# sif_mod.net
KiCad netlist of a schematic drawn in EAGLE
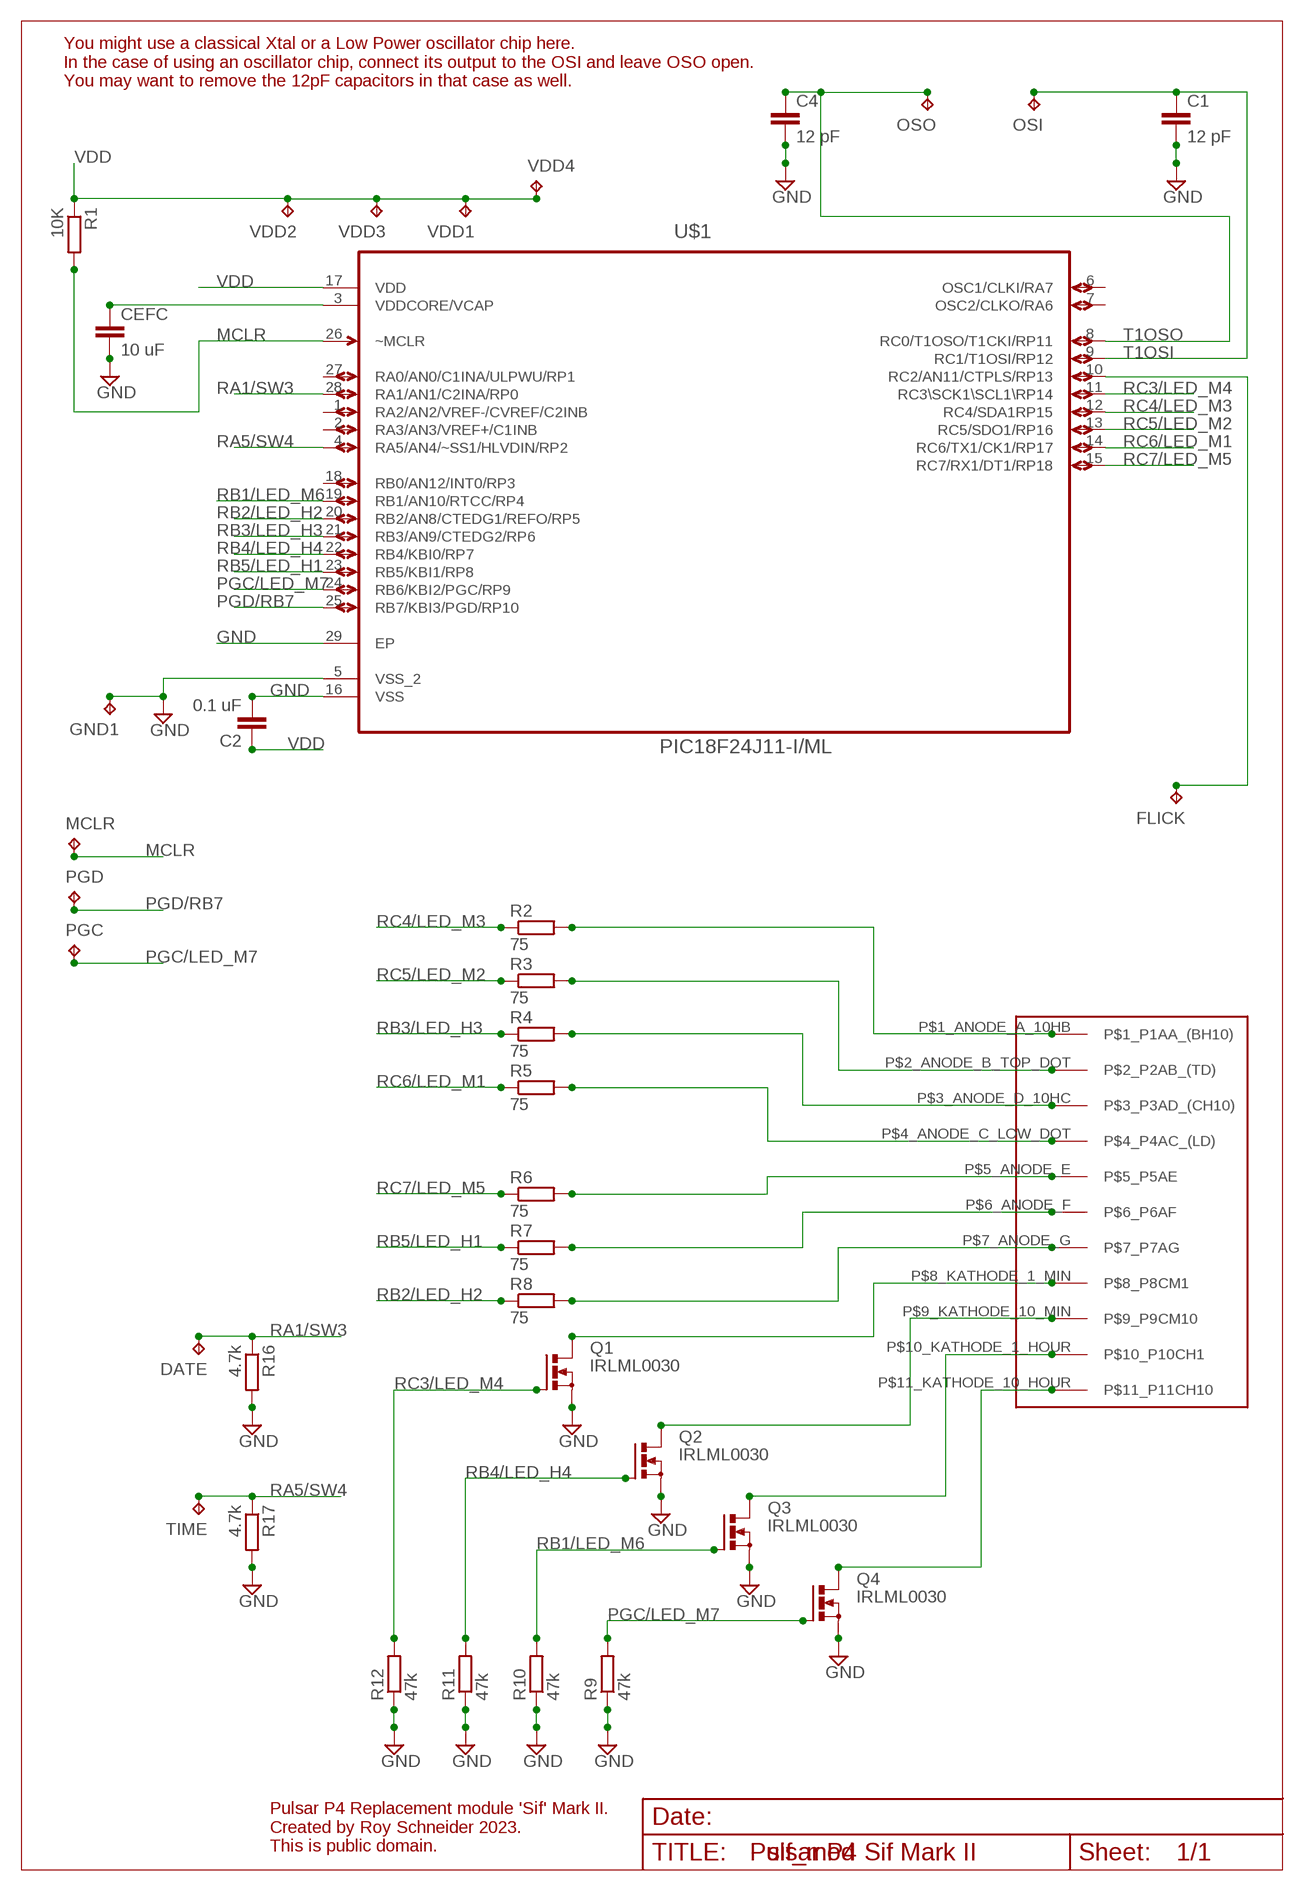
[diagram p0: schematic, sheet 1]

(export (version "E")
  (design (tool "Eeschema 10.0.6"))
  (components
    (comp (ref "C1")
      (value "12 pF")
      (footprint "eagle-import:C0402K")
      (libsource (lib "eagle-import") (part "resistor_mod_C-EUC0402K"))
    )
    (comp (ref "C2")
      (value "0.1 uF")
      (footprint "eagle-import:C0402K")
      (libsource (lib "eagle-import") (part "resistor_mod_C-EUC0402K"))
    )
    (comp (ref "C4")
      (value "12 pF")
      (footprint "eagle-import:C0402K")
      (libsource (lib "eagle-import") (part "resistor_mod_C-EUC0402K"))
    )
    (comp (ref "CEFC")
      (value "10 uF")
      (footprint "eagle-import:C0603")
      (libsource (lib "eagle-import") (part "C-EUC0603"))
    )
    (comp (ref "DATE")
      (value "TPTP08SQ")
      (footprint "eagle-import:TP08SQ")
      (libsource (lib "eagle-import") (part "TPTP08SQ"))
    )
    (comp (ref "FLICK")
      (value "TPTP08SQ")
      (footprint "eagle-import:TP08SQ")
      (libsource (lib "eagle-import") (part "TPTP08SQ"))
    )
    (comp (ref "GND1")
      (value "TPTP08SQ")
      (footprint "eagle-import:TP08SQ")
      (libsource (lib "eagle-import") (part "TPTP08SQ"))
    )
    (comp (ref "MCLR")
      (value "TPTP06SQ")
      (footprint "eagle-import:TP06SQ")
      (libsource (lib "eagle-import") (part "TPTP06SQ"))
    )
    (comp (ref "OSI")
      (value "TPTP08SQ")
      (footprint "eagle-import:TP08SQ")
      (libsource (lib "eagle-import") (part "TPTP08SQ"))
    )
    (comp (ref "OSO")
      (value "TPTP08SQ")
      (footprint "eagle-import:TP08SQ")
      (libsource (lib "eagle-import") (part "TPTP08SQ"))
    )
    (comp (ref "PGC")
      (value "TPTP06SQ")
      (footprint "eagle-import:TP06SQ")
      (libsource (lib "eagle-import") (part "TPTP06SQ"))
    )
    (comp (ref "PGD")
      (value "TPTP06SQ")
      (footprint "eagle-import:TP06SQ")
      (libsource (lib "eagle-import") (part "TPTP06SQ"))
    )
    (comp (ref "Q1")
      (value "IRLML0030")
      (footprint "eagle-import:SOT-23")
      (libsource (lib "eagle-import") (part "IRLML0030"))
    )
    (comp (ref "Q2")
      (value "IRLML0030")
      (footprint "eagle-import:SOT-23")
      (libsource (lib "eagle-import") (part "IRLML0030"))
    )
    (comp (ref "Q3")
      (value "IRLML0030")
      (footprint "eagle-import:SOT-23")
      (libsource (lib "eagle-import") (part "IRLML0030"))
    )
    (comp (ref "Q4")
      (value "IRLML0030")
      (footprint "eagle-import:SOT-23")
      (libsource (lib "eagle-import") (part "IRLML0030"))
    )
    (comp (ref "R1")
      (value "10K")
      (footprint "eagle-import:R0402")
      (libsource (lib "eagle-import") (part "R-EU_R0402"))
    )
    (comp (ref "R2")
      (value "75")
      (footprint "eagle-import:R0402")
      (libsource (lib "eagle-import") (part "R-EU_R0402"))
    )
    (comp (ref "R3")
      (value "75")
      (footprint "eagle-import:R0402")
      (libsource (lib "eagle-import") (part "R-EU_R0402"))
    )
    (comp (ref "R4")
      (value "75")
      (footprint "eagle-import:R0402")
      (libsource (lib "eagle-import") (part "R-EU_R0402"))
    )
    (comp (ref "R5")
      (value "75")
      (footprint "eagle-import:R0402")
      (libsource (lib "eagle-import") (part "R-EU_R0402"))
    )
    (comp (ref "R6")
      (value "75")
      (footprint "eagle-import:R0402")
      (libsource (lib "eagle-import") (part "R-EU_R0402"))
    )
    (comp (ref "R7")
      (value "75")
      (footprint "eagle-import:R0402")
      (libsource (lib "eagle-import") (part "R-EU_R0402"))
    )
    (comp (ref "R8")
      (value "75")
      (footprint "eagle-import:R0402")
      (libsource (lib "eagle-import") (part "R-EU_R0402"))
    )
    (comp (ref "R9")
      (value "47k")
      (footprint "eagle-import:R0402")
      (libsource (lib "eagle-import") (part "R-EU_R0402"))
    )
    (comp (ref "R10")
      (value "47k")
      (footprint "eagle-import:R0402")
      (libsource (lib "eagle-import") (part "R-EU_R0402"))
    )
    (comp (ref "R11")
      (value "47k")
      (footprint "eagle-import:R0402")
      (libsource (lib "eagle-import") (part "R-EU_R0402"))
    )
    (comp (ref "R12")
      (value "47k")
      (footprint "eagle-import:R0402")
      (libsource (lib "eagle-import") (part "R-EU_R0402"))
    )
    (comp (ref "R16")
      (value "4.7k")
      (footprint "eagle-import:R0402")
      (libsource (lib "eagle-import") (part "R-EU_R0402"))
    )
    (comp (ref "R17")
      (value "4.7k")
      (footprint "eagle-import:R0402")
      (libsource (lib "eagle-import") (part "R-EU_R0402"))
    )
    (comp (ref "TIME")
      (value "TPTP08SQ")
      (footprint "eagle-import:TP08SQ")
      (libsource (lib "eagle-import") (part "TPTP08SQ"))
    )
    (comp (ref "U$1")
      (value "PIC18F24J11-I/ML")
      (footprint "eagle-import:QFN65P600X600X100-29N")
      (fields (field (name "MPN") "PIC18F24J11-I/Ml"))
      (libsource (lib "eagle-import") (part "PIC18F24J11-I/ML"))
    )
    (comp (ref "U$2")
      (value "PULSAR_P4_DISPLAYPULSAR_P4_LED_DISPLAY")
      (footprint "eagle-import:PULSAR_P3_LED_DISPLAY")
      (libsource (lib "eagle-import") (part "PULSAR_P4_DISPLAYPULSAR_P4_LED_DISPLAY"))
    )
    (comp (ref "VDD1")
      (value "TPTP08SQ")
      (footprint "eagle-import:TP08SQ")
      (libsource (lib "eagle-import") (part "TPTP08SQ"))
    )
    (comp (ref "VDD2")
      (value "TPTP08SQ")
      (footprint "eagle-import:TP08SQ")
      (libsource (lib "eagle-import") (part "TPTP08SQ"))
    )
    (comp (ref "VDD3")
      (value "TPTP08SQ")
      (footprint "eagle-import:TP08SQ")
      (libsource (lib "eagle-import") (part "TPTP08SQ"))
    )
    (comp (ref "VDD4")
      (value "TPTP08SQ")
      (footprint "eagle-import:TP08SQ")
      (libsource (lib "eagle-import") (part "TPTP08SQ"))
    )
  )
  (nets
    (net (code "1") (name "/MCLR") (class "Default")
      (node (ref "MCLR") (pin "TP") (pinfunction "TP_TP") (pintype "input"))
      (node (ref "R1") (pin "2") (pinfunction "2_2") (pintype "passive"))
      (node (ref "U$1") (pin "26") (pinfunction "~{MCLR}_26") (pintype "input"))
    )
    (net (code "2") (name "/PGC{slash}LED_M7") (class "Default")
      (node (ref "PGC") (pin "TP") (pinfunction "TP_TP") (pintype "input"))
      (node (ref "Q4") (pin "P1") (pinfunction "G_P1") (pintype "passive"))
      (node (ref "R9") (pin "2") (pinfunction "2_2") (pintype "passive"))
      (node (ref "U$1") (pin "24") (pinfunction "RB6/KBI2/PGC/RP9_24") (pintype "bidirectional"))
    )
    (net (code "3") (name "/PGD{slash}RB7") (class "Default")
      (node (ref "PGD") (pin "TP") (pinfunction "TP_TP") (pintype "input"))
      (node (ref "U$1") (pin "25") (pinfunction "RB7/KBI3/PGD/RP10_25") (pintype "bidirectional"))
    )
    (net (code "4") (name "/RA1{slash}SW3") (class "Default")
      (node (ref "DATE") (pin "TP") (pinfunction "TP_TP") (pintype "input"))
      (node (ref "R16") (pin "1") (pinfunction "1_1") (pintype "passive"))
      (node (ref "U$1") (pin "28") (pinfunction "RA1/AN1/C2INA/RP0_28") (pintype "bidirectional"))
    )
    (net (code "5") (name "/RA5{slash}SW4") (class "Default")
      (node (ref "R17") (pin "1") (pinfunction "1_1") (pintype "passive"))
      (node (ref "TIME") (pin "TP") (pinfunction "TP_TP") (pintype "input"))
      (node (ref "U$1") (pin "4") (pinfunction "RA5/AN4/~{SS1/HLVDIN/RP2}_4") (pintype "bidirectional"))
    )
    (net (code "6") (name "/RB1{slash}LED_M6") (class "Default")
      (node (ref "Q3") (pin "P1") (pinfunction "G_P1") (pintype "passive"))
      (node (ref "R10") (pin "2") (pinfunction "2_2") (pintype "passive"))
      (node (ref "U$1") (pin "19") (pinfunction "RB1/AN10/RTCC/RP4_19") (pintype "bidirectional"))
    )
    (net (code "7") (name "/RB2{slash}LED_H2") (class "Default")
      (node (ref "R8") (pin "1") (pinfunction "1_1") (pintype "passive"))
      (node (ref "U$1") (pin "20") (pinfunction "RB2/AN8/CTEDG1/REFO/RP5_20") (pintype "bidirectional"))
    )
    (net (code "8") (name "/RB3{slash}LED_H3") (class "Default")
      (node (ref "R4") (pin "1") (pinfunction "1_1") (pintype "passive"))
      (node (ref "U$1") (pin "21") (pinfunction "RB3/AN9/CTEDG2/RP6_21") (pintype "bidirectional"))
    )
    (net (code "9") (name "/RB4{slash}LED_H4") (class "Default")
      (node (ref "Q2") (pin "P1") (pinfunction "G_P1") (pintype "passive"))
      (node (ref "R11") (pin "2") (pinfunction "2_2") (pintype "passive"))
      (node (ref "U$1") (pin "22") (pinfunction "RB4/KBI0/RP7_22") (pintype "bidirectional"))
    )
    (net (code "10") (name "/RB5{slash}LED_H1") (class "Default")
      (node (ref "R7") (pin "1") (pinfunction "1_1") (pintype "passive"))
      (node (ref "U$1") (pin "23") (pinfunction "RB5/KBI1/RP8_23") (pintype "bidirectional"))
    )
    (net (code "11") (name "/RC3{slash}LED_M4") (class "Default")
      (node (ref "Q1") (pin "P1") (pinfunction "G_P1") (pintype "passive"))
      (node (ref "R12") (pin "2") (pinfunction "2_2") (pintype "passive"))
      (node (ref "U$1") (pin "11") (pinfunction "RC3\\SCK1\\SCL1\\RP14_11") (pintype "bidirectional"))
    )
    (net (code "12") (name "/RC4{slash}LED_M3") (class "Default")
      (node (ref "R2") (pin "1") (pinfunction "1_1") (pintype "passive"))
      (node (ref "U$1") (pin "12") (pinfunction "RC4/SDA1RP15_12") (pintype "bidirectional"))
    )
    (net (code "13") (name "/RC5{slash}LED_M2") (class "Default")
      (node (ref "R3") (pin "1") (pinfunction "1_1") (pintype "passive"))
      (node (ref "U$1") (pin "13") (pinfunction "RC5/SDO1/RP16_13") (pintype "bidirectional"))
    )
    (net (code "14") (name "/RC6{slash}LED_M1") (class "Default")
      (node (ref "R5") (pin "1") (pinfunction "1_1") (pintype "passive"))
      (node (ref "U$1") (pin "14") (pinfunction "RC6/TX1/CK1/RP17_14") (pintype "bidirectional"))
    )
    (net (code "15") (name "/RC7{slash}LED_M5") (class "Default")
      (node (ref "R6") (pin "1") (pinfunction "1_1") (pintype "passive"))
      (node (ref "U$1") (pin "15") (pinfunction "RC7/RX1/DT1/RP18_15") (pintype "bidirectional"))
    )
    (net (code "16") (name "/T1OSI") (class "Default")
      (node (ref "C1") (pin "1") (pinfunction "1_1") (pintype "passive"))
      (node (ref "OSI") (pin "TP") (pinfunction "TP_TP") (pintype "input"))
      (node (ref "U$1") (pin "9") (pinfunction "RC1/T1OSI/RP12_9") (pintype "bidirectional"))
    )
    (net (code "17") (name "/T1OSO") (class "Default")
      (node (ref "C4") (pin "1") (pinfunction "1_1") (pintype "passive"))
      (node (ref "OSO") (pin "TP") (pinfunction "TP_TP") (pintype "input"))
      (node (ref "U$1") (pin "8") (pinfunction "RC0/T1OSO/T1CKI/RP11_8") (pintype "bidirectional"))
    )
    (net (code "18") (name "/VDD") (class "Default")
      (node (ref "C2") (pin "1") (pinfunction "1_1") (pintype "passive"))
      (node (ref "R1") (pin "1") (pinfunction "1_1") (pintype "passive"))
      (node (ref "U$1") (pin "17") (pinfunction "VDD_17") (pintype "power_in"))
      (node (ref "VDD1") (pin "TP") (pinfunction "TP_TP") (pintype "input"))
      (node (ref "VDD2") (pin "TP") (pinfunction "TP_TP") (pintype "input"))
      (node (ref "VDD3") (pin "TP") (pinfunction "TP_TP") (pintype "input"))
      (node (ref "VDD4") (pin "TP") (pinfunction "TP_TP") (pintype "input"))
    )
    (net (code "19") (name "GND") (class "Default")
      (node (ref "C1") (pin "2") (pinfunction "2_2") (pintype "passive"))
      (node (ref "C2") (pin "2") (pinfunction "2_2") (pintype "passive"))
      (node (ref "C4") (pin "2") (pinfunction "2_2") (pintype "passive"))
      (node (ref "CEFC") (pin "2") (pinfunction "2_2") (pintype "passive"))
      (node (ref "GND1") (pin "TP") (pinfunction "TP_TP") (pintype "input"))
      (node (ref "Q1") (pin "P2") (pinfunction "S_P2") (pintype "passive"))
      (node (ref "Q2") (pin "P2") (pinfunction "S_P2") (pintype "passive"))
      (node (ref "Q3") (pin "P2") (pinfunction "S_P2") (pintype "passive"))
      (node (ref "Q4") (pin "P2") (pinfunction "S_P2") (pintype "passive"))
      (node (ref "R10") (pin "1") (pinfunction "1_1") (pintype "passive"))
      (node (ref "R11") (pin "1") (pinfunction "1_1") (pintype "passive"))
      (node (ref "R12") (pin "1") (pinfunction "1_1") (pintype "passive"))
      (node (ref "R16") (pin "2") (pinfunction "2_2") (pintype "passive"))
      (node (ref "R17") (pin "2") (pinfunction "2_2") (pintype "passive"))
      (node (ref "R9") (pin "1") (pinfunction "1_1") (pintype "passive"))
      (node (ref "U$1") (pin "16") (pinfunction "VSS_16") (pintype "passive"))
      (node (ref "U$1") (pin "29") (pinfunction "EP_29") (pintype "passive"))
      (node (ref "U$1") (pin "5") (pinfunction "VSS_2_5") (pintype "passive"))
    )
    (net (code "20") (name "Net-(Q1-D)") (class "Default")
      (node (ref "Q1") (pin "P3") (pinfunction "D_P3") (pintype "passive"))
      (node (ref "U$2") (pin "P$8_KATHODE_1_MIN") (pinfunction "P$8_P8CM1_P$8_KATHODE_1_MIN") (pintype "bidirectional"))
    )
    (net (code "21") (name "Net-(Q2-D)") (class "Default")
      (node (ref "Q2") (pin "P3") (pinfunction "D_P3") (pintype "passive"))
      (node (ref "U$2") (pin "P$9_KATHODE_10_MIN") (pinfunction "P$9_P9CM10_P$9_KATHODE_10_MIN") (pintype "bidirectional"))
    )
    (net (code "22") (name "Net-(Q3-D)") (class "Default")
      (node (ref "Q3") (pin "P3") (pinfunction "D_P3") (pintype "passive"))
      (node (ref "U$2") (pin "P$10_KATHODE_1_HOUR") (pinfunction "P$10_P10CH1_P$10_KATHODE_1_HOUR") (pintype "bidirectional"))
    )
    (net (code "23") (name "Net-(Q4-D)") (class "Default")
      (node (ref "Q4") (pin "P3") (pinfunction "D_P3") (pintype "passive"))
      (node (ref "U$2") (pin "P$11_KATHODE_10_HOUR") (pinfunction "P$11_P11CH10_P$11_KATHODE_10_HOUR") (pintype "bidirectional"))
    )
    (net (code "24") (name "Net-(U$1-RC2{slash}AN11{slash}CTPLS{slash}RP13)") (class "Default")
      (node (ref "FLICK") (pin "TP") (pinfunction "TP_TP") (pintype "input"))
      (node (ref "U$1") (pin "10") (pinfunction "RC2/AN11/CTPLS/RP13_10") (pintype "bidirectional"))
    )
    (net (code "25") (name "Net-(U$1-VDDCORE{slash}VCAP)") (class "Default")
      (node (ref "CEFC") (pin "1") (pinfunction "1_1") (pintype "passive"))
      (node (ref "U$1") (pin "3") (pinfunction "VDDCORE/VCAP_3") (pintype "power_in"))
    )
    (net (code "26") (name "Net-(U$2-P$1_P1AA_(BH10))") (class "Default")
      (node (ref "R2") (pin "2") (pinfunction "2_2") (pintype "passive"))
      (node (ref "U$2") (pin "P$1_ANODE_A_10HB") (pinfunction "P$1_P1AA_(BH10)_P$1_ANODE_A_10HB") (pintype "bidirectional"))
    )
    (net (code "27") (name "Net-(U$2-P$2_P2AB_(TD))") (class "Default")
      (node (ref "R3") (pin "2") (pinfunction "2_2") (pintype "passive"))
      (node (ref "U$2") (pin "P$2_ANODE_B_TOP_DOT") (pinfunction "P$2_P2AB_(TD)_P$2_ANODE_B_TOP_DOT") (pintype "bidirectional"))
    )
    (net (code "28") (name "Net-(U$2-P$3_P3AD_(CH10))") (class "Default")
      (node (ref "R4") (pin "2") (pinfunction "2_2") (pintype "passive"))
      (node (ref "U$2") (pin "P$3_ANODE_D_10HC") (pinfunction "P$3_P3AD_(CH10)_P$3_ANODE_D_10HC") (pintype "bidirectional"))
    )
    (net (code "29") (name "Net-(U$2-P$4_P4AC_(LD))") (class "Default")
      (node (ref "R5") (pin "2") (pinfunction "2_2") (pintype "passive"))
      (node (ref "U$2") (pin "P$4_ANODE_C_LOW_DOT") (pinfunction "P$4_P4AC_(LD)_P$4_ANODE_C_LOW_DOT") (pintype "bidirectional"))
    )
    (net (code "30") (name "Net-(U$2-P$5_P5AE)") (class "Default")
      (node (ref "R6") (pin "2") (pinfunction "2_2") (pintype "passive"))
      (node (ref "U$2") (pin "P$5_ANODE_E") (pinfunction "P$5_P5AE_P$5_ANODE_E") (pintype "bidirectional"))
    )
    (net (code "31") (name "Net-(U$2-P$6_P6AF)") (class "Default")
      (node (ref "R7") (pin "2") (pinfunction "2_2") (pintype "passive"))
      (node (ref "U$2") (pin "P$6_ANODE_F") (pinfunction "P$6_P6AF_P$6_ANODE_F") (pintype "bidirectional"))
    )
    (net (code "32") (name "Net-(U$2-P$7_P7AG)") (class "Default")
      (node (ref "R8") (pin "2") (pinfunction "2_2") (pintype "passive"))
      (node (ref "U$2") (pin "P$7_ANODE_G") (pinfunction "P$7_P7AG_P$7_ANODE_G") (pintype "bidirectional"))
    )
    (net (code "33") (name "unconnected-(U$1-OSC1{slash}CLKI{slash}RA7-Pad6)") (class "Default")
      (node (ref "U$1") (pin "6") (pinfunction "OSC1/CLKI/RA7_6") (pintype "bidirectional"))
    )
    (net (code "34") (name "unconnected-(U$1-OSC2{slash}CLKO{slash}RA6-Pad7)") (class "Default")
      (node (ref "U$1") (pin "7") (pinfunction "OSC2/CLKO/RA6_7") (pintype "bidirectional"))
    )
    (net (code "35") (name "unconnected-(U$1-RA0{slash}AN0{slash}C1INA{slash}ULPWU{slash}RP1-Pad27)") (class "Default")
      (node (ref "U$1") (pin "27") (pinfunction "RA0/AN0/C1INA/ULPWU/RP1_27") (pintype "bidirectional"))
    )
    (net (code "36") (name "unconnected-(U$1-RA2{slash}AN2{slash}VREF-{slash}CVREF{slash}C2INB-Pad1)") (class "Default")
      (node (ref "U$1") (pin "1") (pinfunction "RA2/AN2/VREF-/CVREF/C2INB_1") (pintype "bidirectional"))
    )
    (net (code "37") (name "unconnected-(U$1-RA3{slash}AN3{slash}VREF+{slash}C1INB-Pad2)") (class "Default")
      (node (ref "U$1") (pin "2") (pinfunction "RA3/AN3/VREF+/C1INB_2") (pintype "bidirectional"))
    )
    (net (code "38") (name "unconnected-(U$1-RB0{slash}AN12{slash}INT0{slash}RP3-Pad18)") (class "Default")
      (node (ref "U$1") (pin "18") (pinfunction "RB0/AN12/INT0/RP3_18") (pintype "bidirectional"))
    )
  )
)
